# onion_dip_v21.net
KiCad netlist of a schematic drawn in EAGLE
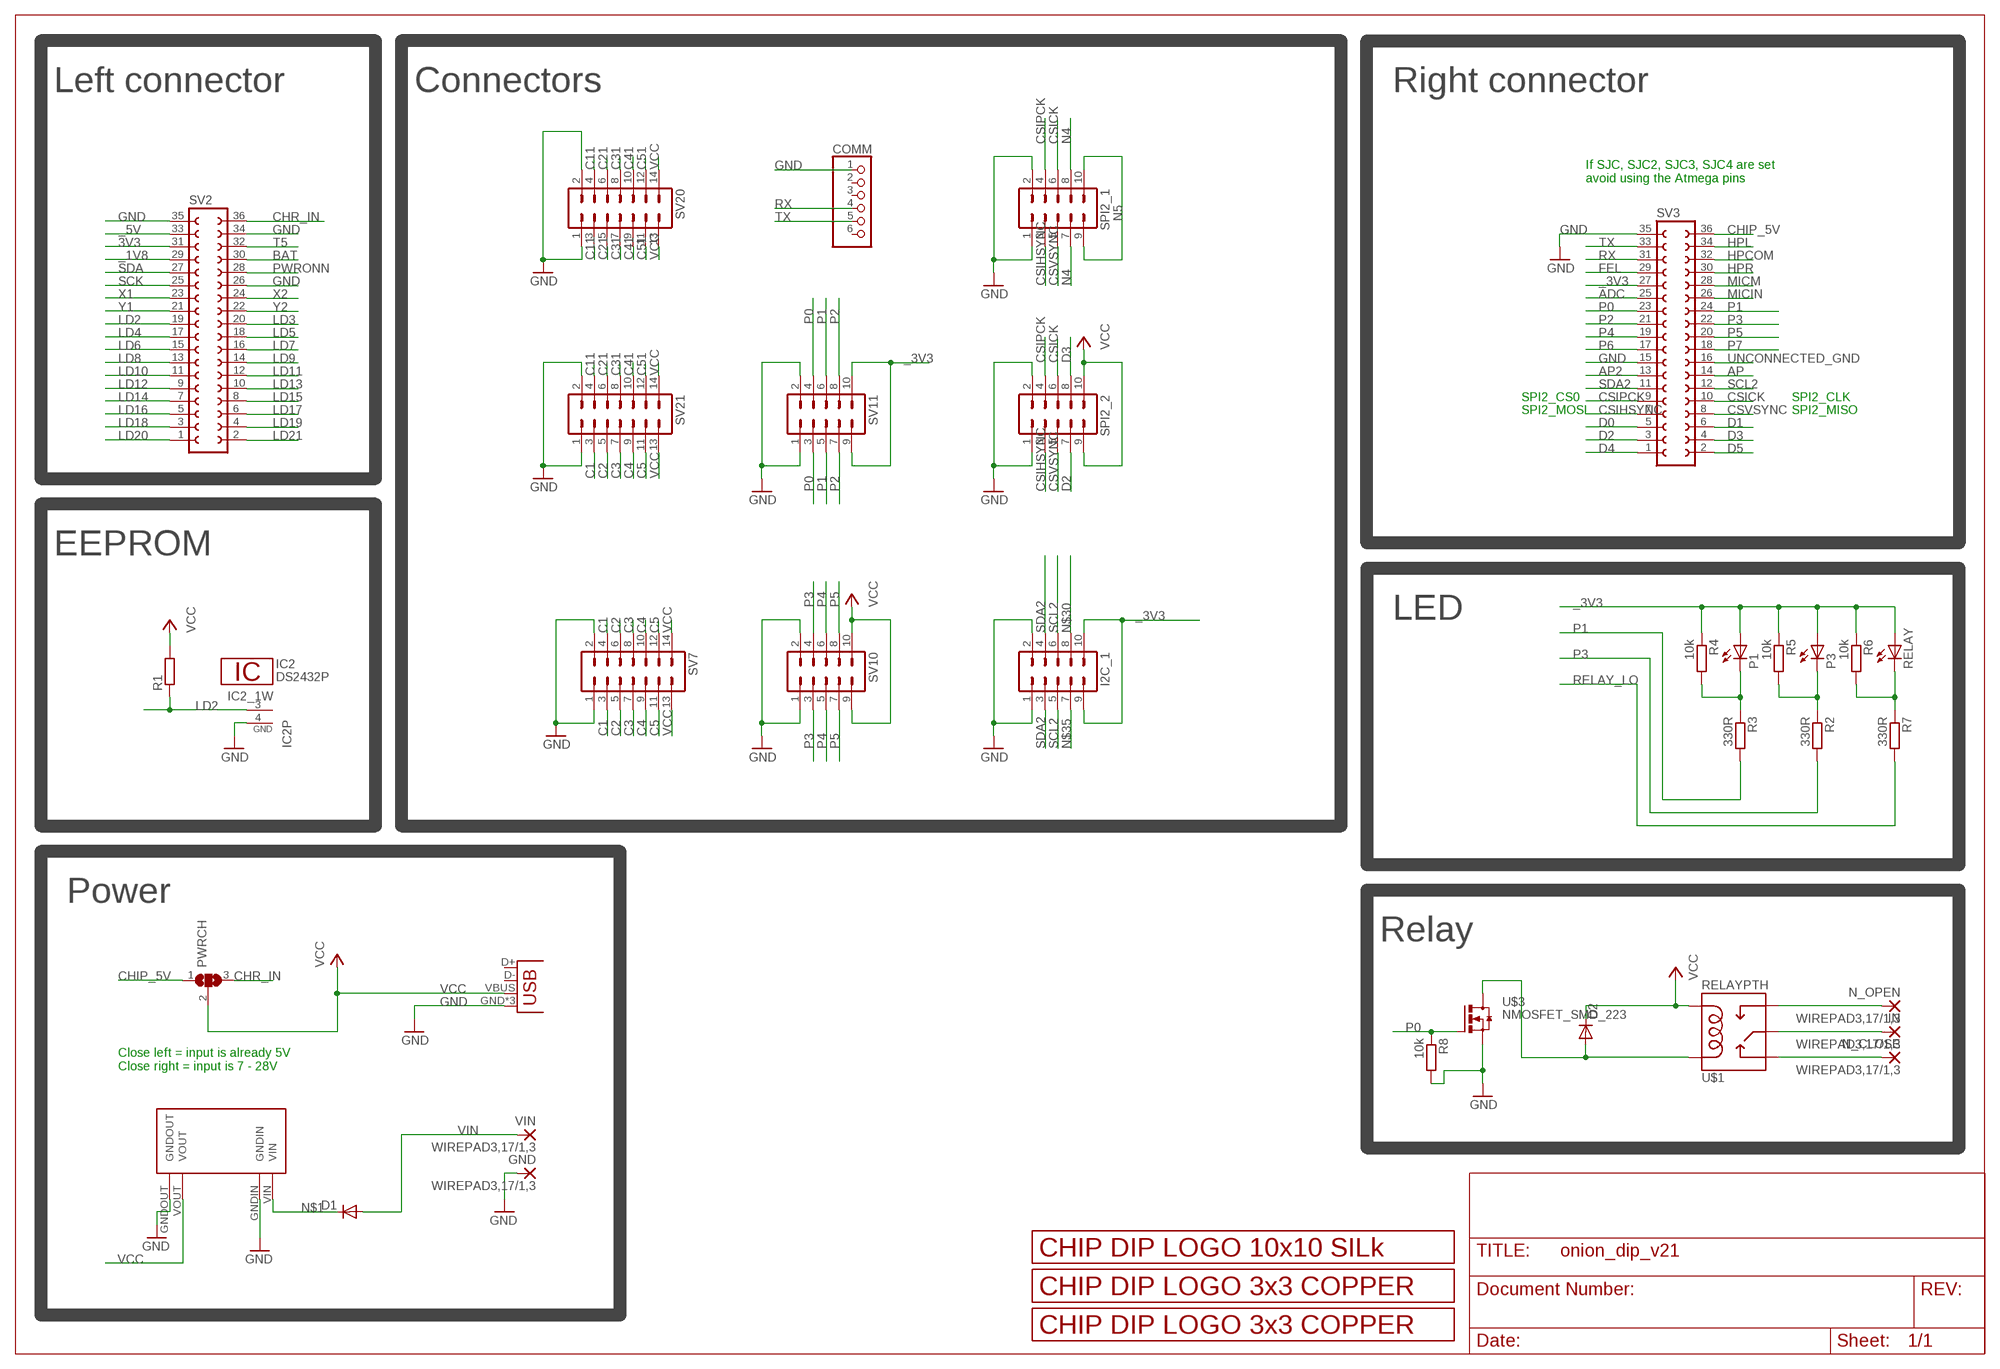
[diagram p0: schematic, sheet 1]

(export (version "E")
  (design (tool "Eeschema 10.0.6"))
  (components
    (comp (ref "COMM")
      (value "PINHD-1X6")
      (footprint "eagle-import:1X06")
      (libsource (lib "eagle-import") (part "PINHD-1X6"))
    )
    (comp (ref "D1")
      (value "DIODE-SMB")
      (footprint "eagle-import:SMB")
      (libsource (lib "eagle-import") (part "DIODE-SMB"))
    )
    (comp (ref "D2")
      (value "DIODE-SMB")
      (footprint "eagle-import:SMB")
      (libsource (lib "eagle-import") (part "DIODE-SMB"))
    )
    (comp (ref "GND")
      (value "WIREPAD3,17/1,3")
      (footprint "eagle-import:3,17_1,3")
      (libsource (lib "eagle-import") (part "WIREPAD3,17/1,3"))
    )
    (comp (ref "I2C_1")
      (value "MA05-2")
      (footprint "eagle-import:MA05-2")
      (libsource (lib "eagle-import") (part "MA05-2"))
    )
    (comp (ref "IC2")
      (value "DS2432P")
      (footprint "eagle-import:TSOC6")
      (libsource (lib "eagle-import") (part "DS2432P"))
    )
    (comp (ref "IN")
      (value "WIREPAD3,17/1,3")
      (footprint "eagle-import:3,17_1,3")
      (libsource (lib "eagle-import") (part "WIREPAD3,17/1,3"))
    )
    (comp (ref "N_CLOSE")
      (value "WIREPAD3,17/1,3")
      (footprint "eagle-import:3,17_1,3")
      (libsource (lib "eagle-import") (part "WIREPAD3,17/1,3"))
    )
    (comp (ref "N_OPEN")
      (value "WIREPAD3,17/1,3")
      (footprint "eagle-import:3,17_1,3")
      (libsource (lib "eagle-import") (part "WIREPAD3,17/1,3"))
    )
    (comp (ref "P1")
      (value "LEDCHIP-LED0805")
      (footprint "eagle-import:CHIP-LED0805")
      (libsource (lib "eagle-import") (part "LEDCHIP-LED0805"))
    )
    (comp (ref "P3")
      (value "LEDCHIP-LED0805")
      (footprint "eagle-import:CHIP-LED0805")
      (libsource (lib "eagle-import") (part "LEDCHIP-LED0805"))
    )
    (comp (ref "PWRCH")
      (value "SJ2W")
      (footprint "eagle-import:SJ_2")
      (libsource (lib "eagle-import") (part "SJ2W"))
    )
    (comp (ref "R1")
      (value "R-EU_R0805")
      (footprint "eagle-import:R0805")
      (libsource (lib "eagle-import") (part "R-EU_R0805"))
    )
    (comp (ref "R2")
      (value "330R")
      (footprint "eagle-import:R0805")
      (libsource (lib "eagle-import") (part "R-EU_R0805"))
    )
    (comp (ref "R3")
      (value "330R")
      (footprint "eagle-import:R0805")
      (libsource (lib "eagle-import") (part "R-EU_R0805"))
    )
    (comp (ref "R4")
      (value "10k")
      (footprint "eagle-import:R0805")
      (libsource (lib "eagle-import") (part "R-EU_R0805"))
    )
    (comp (ref "R5")
      (value "10k")
      (footprint "eagle-import:R0805")
      (libsource (lib "eagle-import") (part "R-EU_R0805"))
    )
    (comp (ref "R6")
      (value "10k")
      (footprint "eagle-import:R0805")
      (libsource (lib "eagle-import") (part "R-EU_R0805"))
    )
    (comp (ref "R7")
      (value "330R")
      (footprint "eagle-import:R0805")
      (libsource (lib "eagle-import") (part "R-EU_R0805"))
    )
    (comp (ref "R8")
      (value "10k")
      (footprint "eagle-import:R0805")
      (libsource (lib "eagle-import") (part "R-EU_R0805"))
    )
    (comp (ref "RELAY")
      (value "LEDCHIP-LED0805")
      (footprint "eagle-import:CHIP-LED0805")
      (libsource (lib "eagle-import") (part "LEDCHIP-LED0805"))
    )
    (comp (ref "SPI2_1")
      (value "MA05-2")
      (footprint "eagle-import:MA05-2")
      (libsource (lib "eagle-import") (part "MA05-2"))
    )
    (comp (ref "SPI2_2")
      (value "MA05-2")
      (footprint "eagle-import:MA05-2")
      (libsource (lib "eagle-import") (part "MA05-2"))
    )
    (comp (ref "SV2")
      (value "FE18-2")
      (footprint "eagle-import:FE18-2")
      (libsource (lib "eagle-import") (part "FE18-2"))
    )
    (comp (ref "SV3")
      (value "FE18-2")
      (footprint "eagle-import:FE18-2")
      (libsource (lib "eagle-import") (part "FE18-2"))
    )
    (comp (ref "SV7")
      (value "MA07-2")
      (footprint "eagle-import:MA07-2")
      (libsource (lib "eagle-import") (part "MA07-2"))
    )
    (comp (ref "SV10")
      (value "MA05-2")
      (footprint "eagle-import:MA05-2")
      (libsource (lib "eagle-import") (part "MA05-2"))
    )
    (comp (ref "SV11")
      (value "MA05-2")
      (footprint "eagle-import:MA05-2")
      (libsource (lib "eagle-import") (part "MA05-2"))
    )
    (comp (ref "SV20")
      (value "MA07-2")
      (footprint "eagle-import:MA07-2")
      (libsource (lib "eagle-import") (part "MA07-2"))
    )
    (comp (ref "SV21")
      (value "MA07-2")
      (footprint "eagle-import:MA07-2")
      (libsource (lib "eagle-import") (part "MA07-2"))
    )
    (comp (ref "U$1")
      (value "RELAYPTH")
      (footprint "eagle-import:SRD-05VDC-SL-C")
      (libsource (lib "eagle-import") (part "RELAYPTH"))
    )
    (comp (ref "U$3")
      (value "NMOSFET_SMD_223")
      (footprint "eagle-import:SOT223")
      (libsource (lib "eagle-import") (part "NMOSFET_SMD_223"))
    )
    (comp (ref "U$4")
      (value "LOGO_3X3_COPPER")
      (footprint "eagle-import:LOGO_3X3_COPPER")
      (libsource (lib "eagle-import") (part "LOGO_3X3_COPPER"))
    )
    (comp (ref "U$5")
      (value "LOGO_10X10_SILK")
      (footprint "eagle-import:LOGO_10X10_SILK")
      (libsource (lib "eagle-import") (part "LOGO_10X10_SILK"))
    )
    (comp (ref "U$6")
      (value "LOGO_3X3_COPPER")
      (footprint "eagle-import:LOGO_3X3_COPPER")
      (libsource (lib "eagle-import") (part "LOGO_3X3_COPPER"))
    )
    (comp (ref "U$9")
      (value "MP1584EN_FRAMELESS")
      (footprint "eagle-import:MP1584EN_FRAMELESS")
      (libsource (lib "eagle-import") (part "MP1584EN_FRAMELESS"))
    )
    (comp (ref "USB")
      (value "USBUSB-MICROB-SMT-DIP")
      (footprint "eagle-import:USB-MICROB-SMT-DIP")
      (libsource (lib "eagle-import") (part "USBUSB-MICROB-SMT-DIP"))
    )
    (comp (ref "VIN")
      (value "WIREPAD3,17/1,3")
      (footprint "eagle-import:3,17_1,3")
      (libsource (lib "eagle-import") (part "WIREPAD3,17/1,3"))
    )
  )
  (nets
    (net (code "1") (name "/3V3") (class "Default")
      (node (ref "SV2") (pin "31") (pinfunction "31_31") (pintype "passive"))
    )
    (net (code "2") (name "/ADC") (class "Default")
      (node (ref "SV3") (pin "25") (pinfunction "25_25") (pintype "passive"))
    )
    (net (code "3") (name "/AP") (class "Default")
      (node (ref "SV3") (pin "14") (pinfunction "14_14") (pintype "passive"))
    )
    (net (code "4") (name "/AP2") (class "Default")
      (node (ref "SV3") (pin "13") (pinfunction "13_13") (pintype "passive"))
    )
    (net (code "5") (name "/BAT") (class "Default")
      (node (ref "SV2") (pin "30") (pinfunction "30_30") (pintype "passive"))
    )
    (net (code "6") (name "/C1") (class "Default")
      (node (ref "SV21") (pin "3") (pinfunction "3_3") (pintype "passive"))
      (node (ref "SV7") (pin "3") (pinfunction "3_3") (pintype "passive"))
      (node (ref "SV7") (pin "4") (pinfunction "4_4") (pintype "passive"))
    )
    (net (code "7") (name "/C2") (class "Default")
      (node (ref "SV21") (pin "5") (pinfunction "5_5") (pintype "passive"))
      (node (ref "SV7") (pin "5") (pinfunction "5_5") (pintype "passive"))
      (node (ref "SV7") (pin "6") (pinfunction "6_6") (pintype "passive"))
    )
    (net (code "8") (name "/C3") (class "Default")
      (node (ref "SV21") (pin "7") (pinfunction "7_7") (pintype "passive"))
      (node (ref "SV7") (pin "7") (pinfunction "7_7") (pintype "passive"))
      (node (ref "SV7") (pin "8") (pinfunction "8_8") (pintype "passive"))
    )
    (net (code "9") (name "/C4") (class "Default")
      (node (ref "SV21") (pin "9") (pinfunction "9_9") (pintype "passive"))
      (node (ref "SV7") (pin "10") (pinfunction "10_10") (pintype "passive"))
      (node (ref "SV7") (pin "9") (pinfunction "9_9") (pintype "passive"))
    )
    (net (code "10") (name "/C5") (class "Default")
      (node (ref "SV21") (pin "11") (pinfunction "11_11") (pintype "passive"))
      (node (ref "SV7") (pin "11") (pinfunction "11_11") (pintype "passive"))
      (node (ref "SV7") (pin "12") (pinfunction "12_12") (pintype "passive"))
    )
    (net (code "11") (name "/C11") (class "Default")
      (node (ref "SV20") (pin "3") (pinfunction "3_3") (pintype "passive"))
      (node (ref "SV20") (pin "4") (pinfunction "4_4") (pintype "passive"))
      (node (ref "SV21") (pin "4") (pinfunction "4_4") (pintype "passive"))
    )
    (net (code "12") (name "/C21") (class "Default")
      (node (ref "SV20") (pin "5") (pinfunction "5_5") (pintype "passive"))
      (node (ref "SV20") (pin "6") (pinfunction "6_6") (pintype "passive"))
      (node (ref "SV21") (pin "6") (pinfunction "6_6") (pintype "passive"))
    )
    (net (code "13") (name "/C31") (class "Default")
      (node (ref "SV20") (pin "7") (pinfunction "7_7") (pintype "passive"))
      (node (ref "SV20") (pin "8") (pinfunction "8_8") (pintype "passive"))
      (node (ref "SV21") (pin "8") (pinfunction "8_8") (pintype "passive"))
    )
    (net (code "14") (name "/C41") (class "Default")
      (node (ref "SV20") (pin "10") (pinfunction "10_10") (pintype "passive"))
      (node (ref "SV20") (pin "9") (pinfunction "9_9") (pintype "passive"))
      (node (ref "SV21") (pin "10") (pinfunction "10_10") (pintype "passive"))
    )
    (net (code "15") (name "/C51") (class "Default")
      (node (ref "SV20") (pin "11") (pinfunction "11_11") (pintype "passive"))
      (node (ref "SV20") (pin "12") (pinfunction "12_12") (pintype "passive"))
      (node (ref "SV21") (pin "12") (pinfunction "12_12") (pintype "passive"))
    )
    (net (code "16") (name "/CHIP_5V") (class "Default")
      (node (ref "PWRCH") (pin "1") (pinfunction "1_1") (pintype "passive"))
      (node (ref "SV3") (pin "36") (pinfunction "36_36") (pintype "passive"))
    )
    (net (code "17") (name "/CHR_IN") (class "Default")
      (node (ref "PWRCH") (pin "3") (pinfunction "3_3") (pintype "passive"))
      (node (ref "SV2") (pin "36") (pinfunction "36_36") (pintype "passive"))
    )
    (net (code "18") (name "/CSICK") (class "Default")
      (node (ref "SPI2_1") (pin "6") (pinfunction "6_6") (pintype "passive"))
      (node (ref "SPI2_2") (pin "6") (pinfunction "6_6") (pintype "passive"))
      (node (ref "SV3") (pin "10") (pinfunction "10_10") (pintype "passive"))
    )
    (net (code "19") (name "/CSIHSYNC") (class "Default")
      (node (ref "SPI2_1") (pin "3") (pinfunction "3_3") (pintype "passive"))
      (node (ref "SPI2_2") (pin "3") (pinfunction "3_3") (pintype "passive"))
      (node (ref "SV3") (pin "7") (pinfunction "7_7") (pintype "passive"))
    )
    (net (code "20") (name "/CSIPCK") (class "Default")
      (node (ref "SPI2_1") (pin "4") (pinfunction "4_4") (pintype "passive"))
      (node (ref "SPI2_2") (pin "4") (pinfunction "4_4") (pintype "passive"))
      (node (ref "SV3") (pin "9") (pinfunction "9_9") (pintype "passive"))
    )
    (net (code "21") (name "/CSVSYNC") (class "Default")
      (node (ref "SPI2_1") (pin "5") (pinfunction "5_5") (pintype "passive"))
      (node (ref "SPI2_2") (pin "5") (pinfunction "5_5") (pintype "passive"))
      (node (ref "SV3") (pin "8") (pinfunction "8_8") (pintype "passive"))
    )
    (net (code "22") (name "/D0") (class "Default")
      (node (ref "SV3") (pin "5") (pinfunction "5_5") (pintype "passive"))
    )
    (net (code "23") (name "/D1") (class "Default")
      (node (ref "SV3") (pin "6") (pinfunction "6_6") (pintype "passive"))
    )
    (net (code "24") (name "/D2") (class "Default")
      (node (ref "SPI2_2") (pin "7") (pinfunction "7_7") (pintype "passive"))
      (node (ref "SV3") (pin "3") (pinfunction "3_3") (pintype "passive"))
    )
    (net (code "25") (name "/D3") (class "Default")
      (node (ref "SPI2_2") (pin "8") (pinfunction "8_8") (pintype "passive"))
      (node (ref "SV3") (pin "4") (pinfunction "4_4") (pintype "passive"))
    )
    (net (code "26") (name "/D4") (class "Default")
      (node (ref "SV3") (pin "1") (pinfunction "1_1") (pintype "passive"))
    )
    (net (code "27") (name "/D5") (class "Default")
      (node (ref "SV3") (pin "2") (pinfunction "2_2") (pintype "passive"))
    )
    (net (code "28") (name "/FEL") (class "Default")
      (node (ref "SV3") (pin "29") (pinfunction "29_29") (pintype "passive"))
    )
    (net (code "29") (name "/HPCOM") (class "Default")
      (node (ref "SV3") (pin "32") (pinfunction "32_32") (pintype "passive"))
    )
    (net (code "30") (name "/HPL") (class "Default")
      (node (ref "SV3") (pin "34") (pinfunction "34_34") (pintype "passive"))
    )
    (net (code "31") (name "/HPR") (class "Default")
      (node (ref "SV3") (pin "30") (pinfunction "30_30") (pintype "passive"))
    )
    (net (code "32") (name "/LD2") (class "Default")
      (node (ref "IC2") (pin "3") (pinfunction "1W_3") (pintype "power_in"))
      (node (ref "R1") (pin "1") (pinfunction "1_1") (pintype "passive"))
      (node (ref "SV2") (pin "19") (pinfunction "19_19") (pintype "passive"))
    )
    (net (code "33") (name "/LD3") (class "Default")
      (node (ref "SV2") (pin "20") (pinfunction "20_20") (pintype "passive"))
    )
    (net (code "34") (name "/LD4") (class "Default")
      (node (ref "SV2") (pin "17") (pinfunction "17_17") (pintype "passive"))
    )
    (net (code "35") (name "/LD5") (class "Default")
      (node (ref "SV2") (pin "18") (pinfunction "18_18") (pintype "passive"))
    )
    (net (code "36") (name "/LD6") (class "Default")
      (node (ref "SV2") (pin "15") (pinfunction "15_15") (pintype "passive"))
    )
    (net (code "37") (name "/LD7") (class "Default")
      (node (ref "SV2") (pin "16") (pinfunction "16_16") (pintype "passive"))
    )
    (net (code "38") (name "/LD8") (class "Default")
      (node (ref "SV2") (pin "13") (pinfunction "13_13") (pintype "passive"))
    )
    (net (code "39") (name "/LD9") (class "Default")
      (node (ref "SV2") (pin "14") (pinfunction "14_14") (pintype "passive"))
    )
    (net (code "40") (name "/LD10") (class "Default")
      (node (ref "SV2") (pin "11") (pinfunction "11_11") (pintype "passive"))
    )
    (net (code "41") (name "/LD11") (class "Default")
      (node (ref "SV2") (pin "12") (pinfunction "12_12") (pintype "passive"))
    )
    (net (code "42") (name "/LD12") (class "Default")
      (node (ref "SV2") (pin "9") (pinfunction "9_9") (pintype "passive"))
    )
    (net (code "43") (name "/LD13") (class "Default")
      (node (ref "SV2") (pin "10") (pinfunction "10_10") (pintype "passive"))
    )
    (net (code "44") (name "/LD14") (class "Default")
      (node (ref "SV2") (pin "7") (pinfunction "7_7") (pintype "passive"))
    )
    (net (code "45") (name "/LD15") (class "Default")
      (node (ref "SV2") (pin "8") (pinfunction "8_8") (pintype "passive"))
    )
    (net (code "46") (name "/LD16") (class "Default")
      (node (ref "SV2") (pin "5") (pinfunction "5_5") (pintype "passive"))
    )
    (net (code "47") (name "/LD17") (class "Default")
      (node (ref "SV2") (pin "6") (pinfunction "6_6") (pintype "passive"))
    )
    (net (code "48") (name "/LD18") (class "Default")
      (node (ref "SV2") (pin "3") (pinfunction "3_3") (pintype "passive"))
    )
    (net (code "49") (name "/LD19") (class "Default")
      (node (ref "SV2") (pin "4") (pinfunction "4_4") (pintype "passive"))
    )
    (net (code "50") (name "/LD20") (class "Default")
      (node (ref "SV2") (pin "1") (pinfunction "1_1") (pintype "passive"))
    )
    (net (code "51") (name "/LD21") (class "Default")
      (node (ref "SV2") (pin "2") (pinfunction "2_2") (pintype "passive"))
    )
    (net (code "52") (name "/MICIN") (class "Default")
      (node (ref "SV3") (pin "26") (pinfunction "26_26") (pintype "passive"))
    )
    (net (code "53") (name "/MICM") (class "Default")
      (node (ref "SV3") (pin "28") (pinfunction "28_28") (pintype "passive"))
    )
    (net (code "54") (name "/N$1") (class "Default")
      (node (ref "D1") (pin "C") (pinfunction "C_C") (pintype "passive"))
      (node (ref "U$9") (pin "VIN") (pinfunction "VIN_VIN") (pintype "power_in"))
    )
    (net (code "55") (name "/N$30") (class "Default")
      (node (ref "I2C_1") (pin "8") (pinfunction "8_8") (pintype "passive"))
    )
    (net (code "56") (name "/N$35") (class "Default")
      (node (ref "I2C_1") (pin "7") (pinfunction "7_7") (pintype "passive"))
    )
    (net (code "57") (name "/N4") (class "Default")
      (node (ref "SPI2_1") (pin "7") (pinfunction "7_7") (pintype "passive"))
      (node (ref "SPI2_1") (pin "8") (pinfunction "8_8") (pintype "passive"))
    )
    (net (code "58") (name "/N5") (class "Default")
      (node (ref "SPI2_1") (pin "10") (pinfunction "10_10") (pintype "passive"))
      (node (ref "SPI2_1") (pin "9") (pinfunction "9_9") (pintype "passive"))
    )
    (net (code "59") (name "/P0") (class "Default")
      (node (ref "R8") (pin "1") (pinfunction "1_1") (pintype "passive"))
      (node (ref "SV11") (pin "3") (pinfunction "3_3") (pintype "passive"))
      (node (ref "SV11") (pin "4") (pinfunction "4_4") (pintype "passive"))
      (node (ref "SV3") (pin "23") (pinfunction "23_23") (pintype "passive"))
      (node (ref "U$3") (pin "1") (pinfunction "G_1") (pintype "passive"))
    )
    (net (code "60") (name "/P1") (class "Default")
      (node (ref "R3") (pin "2") (pinfunction "2_2") (pintype "passive"))
      (node (ref "SV11") (pin "5") (pinfunction "5_5") (pintype "passive"))
      (node (ref "SV11") (pin "6") (pinfunction "6_6") (pintype "passive"))
      (node (ref "SV3") (pin "24") (pinfunction "24_24") (pintype "passive"))
    )
    (net (code "61") (name "/P2") (class "Default")
      (node (ref "SV11") (pin "7") (pinfunction "7_7") (pintype "passive"))
      (node (ref "SV11") (pin "8") (pinfunction "8_8") (pintype "passive"))
      (node (ref "SV3") (pin "21") (pinfunction "21_21") (pintype "passive"))
    )
    (net (code "62") (name "/P3") (class "Default")
      (node (ref "R2") (pin "2") (pinfunction "2_2") (pintype "passive"))
      (node (ref "SV10") (pin "3") (pinfunction "3_3") (pintype "passive"))
      (node (ref "SV10") (pin "4") (pinfunction "4_4") (pintype "passive"))
      (node (ref "SV3") (pin "22") (pinfunction "22_22") (pintype "passive"))
    )
    (net (code "63") (name "/P4") (class "Default")
      (node (ref "SV10") (pin "5") (pinfunction "5_5") (pintype "passive"))
      (node (ref "SV10") (pin "6") (pinfunction "6_6") (pintype "passive"))
      (node (ref "SV3") (pin "19") (pinfunction "19_19") (pintype "passive"))
    )
    (net (code "64") (name "/P5") (class "Default")
      (node (ref "SV10") (pin "7") (pinfunction "7_7") (pintype "passive"))
      (node (ref "SV10") (pin "8") (pinfunction "8_8") (pintype "passive"))
      (node (ref "SV3") (pin "20") (pinfunction "20_20") (pintype "passive"))
    )
    (net (code "65") (name "/P6") (class "Default")
      (node (ref "SV3") (pin "17") (pinfunction "17_17") (pintype "passive"))
    )
    (net (code "66") (name "/P7") (class "Default")
      (node (ref "SV3") (pin "18") (pinfunction "18_18") (pintype "passive"))
    )
    (net (code "67") (name "/PWRONN") (class "Default")
      (node (ref "SV2") (pin "28") (pinfunction "28_28") (pintype "passive"))
    )
    (net (code "68") (name "/RELAY_LO") (class "Default")
      (node (ref "D2") (pin "A") (pinfunction "A_A") (pintype "passive"))
      (node (ref "R7") (pin "2") (pinfunction "2_2") (pintype "passive"))
      (node (ref "U$1") (pin "COIL1") (pinfunction "COIL1_COIL1") (pintype "bidirectional"))
      (node (ref "U$3") (pin "2") (pinfunction "D_2") (pintype "passive"))
      (node (ref "U$3") (pin "4") (pinfunction "D_4") (pintype "passive"))
    )
    (net (code "69") (name "/RX") (class "Default")
      (node (ref "COMM") (pin "4") (pinfunction "4_4") (pintype "passive"))
      (node (ref "SV3") (pin "31") (pinfunction "31_31") (pintype "passive"))
    )
    (net (code "70") (name "/SCK") (class "Default")
      (node (ref "SV2") (pin "25") (pinfunction "25_25") (pintype "passive"))
    )
    (net (code "71") (name "/SCL2") (class "Default")
      (node (ref "I2C_1") (pin "5") (pinfunction "5_5") (pintype "passive"))
      (node (ref "I2C_1") (pin "6") (pinfunction "6_6") (pintype "passive"))
      (node (ref "SV3") (pin "12") (pinfunction "12_12") (pintype "passive"))
    )
    (net (code "72") (name "/SDA") (class "Default")
      (node (ref "SV2") (pin "27") (pinfunction "27_27") (pintype "passive"))
    )
    (net (code "73") (name "/SDA2") (class "Default")
      (node (ref "I2C_1") (pin "3") (pinfunction "3_3") (pintype "passive"))
      (node (ref "I2C_1") (pin "4") (pinfunction "4_4") (pintype "passive"))
      (node (ref "SV3") (pin "11") (pinfunction "11_11") (pintype "passive"))
    )
    (net (code "74") (name "/T5") (class "Default")
      (node (ref "SV2") (pin "32") (pinfunction "32_32") (pintype "passive"))
    )
    (net (code "75") (name "/TX") (class "Default")
      (node (ref "COMM") (pin "5") (pinfunction "5_5") (pintype "passive"))
      (node (ref "SV3") (pin "33") (pinfunction "33_33") (pintype "passive"))
    )
    (net (code "76") (name "/UNCONNECTED_GND") (class "Default")
      (node (ref "SV3") (pin "16") (pinfunction "16_16") (pintype "passive"))
    )
    (net (code "77") (name "/VIN") (class "Default")
      (node (ref "D1") (pin "A") (pinfunction "A_A") (pintype "passive"))
      (node (ref "VIN") (pin "1") (pinfunction "P_1") (pintype "passive"))
    )
    (net (code "78") (name "/X1") (class "Default")
      (node (ref "SV2") (pin "23") (pinfunction "23_23") (pintype "passive"))
    )
    (net (code "79") (name "/X2") (class "Default")
      (node (ref "SV2") (pin "24") (pinfunction "24_24") (pintype "passive"))
    )
    (net (code "80") (name "/Y1") (class "Default")
      (node (ref "SV2") (pin "21") (pinfunction "21_21") (pintype "passive"))
    )
    (net (code "81") (name "/Y2") (class "Default")
      (node (ref "SV2") (pin "22") (pinfunction "22_22") (pintype "passive"))
    )
    (net (code "82") (name "/_1V8") (class "Default")
      (node (ref "SV2") (pin "29") (pinfunction "29_29") (pintype "passive"))
    )
    (net (code "83") (name "/_3V3") (class "Default")
      (node (ref "I2C_1") (pin "10") (pinfunction "10_10") (pintype "passive"))
      (node (ref "I2C_1") (pin "9") (pinfunction "9_9") (pintype "passive"))
      (node (ref "P1") (pin "A") (pinfunction "A_A") (pintype "passive"))
      (node (ref "P3") (pin "A") (pinfunction "A_A") (pintype "passive"))
      (node (ref "R4") (pin "1") (pinfunction "1_1") (pintype "passive"))
      (node (ref "R5") (pin "1") (pinfunction "1_1") (pintype "passive"))
      (node (ref "R6") (pin "1") (pinfunction "1_1") (pintype "passive"))
      (node (ref "RELAY") (pin "A") (pinfunction "A_A") (pintype "passive"))
      (node (ref "SV11") (pin "10") (pinfunction "10_10") (pintype "passive"))
      (node (ref "SV11") (pin "9") (pinfunction "9_9") (pintype "passive"))
      (node (ref "SV3") (pin "27") (pinfunction "27_27") (pintype "passive"))
    )
    (net (code "84") (name "/_5V") (class "Default")
      (node (ref "SV2") (pin "33") (pinfunction "33_33") (pintype "passive"))
    )
    (net (code "85") (name "GND") (class "Default")
      (node (ref "COMM") (pin "1") (pinfunction "1_1") (pintype "passive"))
      (node (ref "GND") (pin "1") (pinfunction "P_1") (pintype "passive"))
      (node (ref "I2C_1") (pin "1") (pinfunction "1_1") (pintype "passive"))
      (node (ref "I2C_1") (pin "2") (pinfunction "2_2") (pintype "passive"))
      (node (ref "IC2") (pin "4") (pinfunction "GND_4") (pintype "power_in"))
      (node (ref "R8") (pin "2") (pinfunction "2_2") (pintype "passive"))
      (node (ref "SPI2_1") (pin "1") (pinfunction "1_1") (pintype "passive"))
      (node (ref "SPI2_1") (pin "2") (pinfunction "2_2") (pintype "passive"))
      (node (ref "SPI2_2") (pin "1") (pinfunction "1_1") (pintype "passive"))
      (node (ref "SPI2_2") (pin "2") (pinfunction "2_2") (pintype "passive"))
      (node (ref "SV10") (pin "1") (pinfunction "1_1") (pintype "passive"))
      (node (ref "SV10") (pin "2") (pinfunction "2_2") (pintype "passive"))
      (node (ref "SV11") (pin "1") (pinfunction "1_1") (pintype "passive"))
      (node (ref "SV11") (pin "2") (pinfunction "2_2") (pintype "passive"))
      (node (ref "SV2") (pin "26") (pinfunction "26_26") (pintype "passive"))
      (node (ref "SV2") (pin "34") (pinfunction "34_34") (pintype "passive"))
      (node (ref "SV2") (pin "35") (pinfunction "35_35") (pintype "passive"))
      (node (ref "SV20") (pin "1") (pinfunction "1_1") (pintype "passive"))
      (node (ref "SV20") (pin "2") (pinfunction "2_2") (pintype "passive"))
      (node (ref "SV21") (pin "1") (pinfunction "1_1") (pintype "passive"))
      (node (ref "SV21") (pin "2") (pinfunction "2_2") (pintype "passive"))
      (node (ref "SV3") (pin "15") (pinfunction "15_15") (pintype "passive"))
      (node (ref "SV3") (pin "35") (pinfunction "35_35") (pintype "passive"))
      (node (ref "SV7") (pin "1") (pinfunction "1_1") (pintype "passive"))
      (node (ref "SV7") (pin "2") (pinfunction "2_2") (pintype "passive"))
      (node (ref "U$3") (pin "3") (pinfunction "S_3") (pintype "passive"))
      (node (ref "U$9") (pin "GNDIN") (pinfunction "GNDIN_GNDIN") (pintype "power_in"))
      (node (ref "U$9") (pin "GNDOUT") (pinfunction "GNDOUT_GNDOUT") (pintype "power_in"))
      (node (ref "USB") (pin "GND") (pinfunction "GND_GND") (pintype "bidirectional"))
      (node (ref "USB") (pin "MT1") (pinfunction "GND_MT1") (pintype "bidirectional"))
      (node (ref "USB") (pin "MT2") (pinfunction "GND_MT2") (pintype "bidirectional"))
    )
    (net (code "86") (name "Net-(IN-P)") (class "Default")
      (node (ref "IN") (pin "1") (pinfunction "P_1") (pintype "passive"))
      (node (ref "U$1") (pin "SWCOMMON") (pinfunction "SWCOMMON_SWCOMMON") (pintype "bidirectional"))
    )
    (net (code "87") (name "Net-(N_CLOSE-P)") (class "Default")
      (node (ref "N_CLOSE") (pin "1") (pinfunction "P_1") (pintype "passive"))
      (node (ref "U$1") (pin "SWCLOSED") (pinfunction "SWCLOSE_SWCLOSED") (pintype "bidirectional"))
    )
    (net (code "88") (name "Net-(N_OPEN-P)") (class "Default")
      (node (ref "N_OPEN") (pin "1") (pinfunction "P_1") (pintype "passive"))
      (node (ref "U$1") (pin "SWOPEN") (pinfunction "SWOPEN_SWOPEN") (pintype "bidirectional"))
    )
    (net (code "89") (name "Net-(P1-PadC)") (class "Default")
      (node (ref "P1") (pin "C") (pinfunction "C_C") (pintype "passive"))
      (node (ref "R3") (pin "1") (pinfunction "1_1") (pintype "passive"))
      (node (ref "R4") (pin "2") (pinfunction "2_2") (pintype "passive"))
    )
    (net (code "90") (name "Net-(P3-PadC)") (class "Default")
      (node (ref "P3") (pin "C") (pinfunction "C_C") (pintype "passive"))
      (node (ref "R2") (pin "1") (pinfunction "1_1") (pintype "passive"))
      (node (ref "R5") (pin "2") (pinfunction "2_2") (pintype "passive"))
    )
    (net (code "91") (name "Net-(R6-Pad2)") (class "Default")
      (node (ref "R6") (pin "2") (pinfunction "2_2") (pintype "passive"))
      (node (ref "R7") (pin "1") (pinfunction "1_1") (pintype "passive"))
      (node (ref "RELAY") (pin "C") (pinfunction "C_C") (pintype "passive"))
    )
    (net (code "92") (name "VCC") (class "Default")
      (node (ref "D2") (pin "C") (pinfunction "C_C") (pintype "passive"))
      (node (ref "PWRCH") (pin "2") (pinfunction "2_2") (pintype "passive"))
      (node (ref "R1") (pin "2") (pinfunction "2_2") (pintype "passive"))
      (node (ref "SPI2_2") (pin "10") (pinfunction "10_10") (pintype "passive"))
      (node (ref "SPI2_2") (pin "9") (pinfunction "9_9") (pintype "passive"))
      (node (ref "SV10") (pin "10") (pinfunction "10_10") (pintype "passive"))
      (node (ref "SV10") (pin "9") (pinfunction "9_9") (pintype "passive"))
      (node (ref "SV20") (pin "13") (pinfunction "13_13") (pintype "passive"))
      (node (ref "SV20") (pin "14") (pinfunction "14_14") (pintype "passive"))
      (node (ref "SV21") (pin "13") (pinfunction "13_13") (pintype "passive"))
      (node (ref "SV21") (pin "14") (pinfunction "14_14") (pintype "passive"))
      (node (ref "SV7") (pin "13") (pinfunction "13_13") (pintype "passive"))
      (node (ref "SV7") (pin "14") (pinfunction "14_14") (pintype "passive"))
      (node (ref "U$1") (pin "COIL0") (pinfunction "COIL0_COIL0") (pintype "bidirectional"))
      (node (ref "U$9") (pin "VOUT") (pinfunction "VOUT_VOUT") (pintype "power_in"))
      (node (ref "USB") (pin "VBUS") (pinfunction "VBUS_VBUS") (pintype "bidirectional"))
    )
    (net (code "93") (name "unconnected-(COMM-Pad2)") (class "Default")
      (node (ref "COMM") (pin "2") (pinfunction "2_2") (pintype "passive"))
    )
    (net (code "94") (name "unconnected-(COMM-Pad3)") (class "Default")
      (node (ref "COMM") (pin "3") (pinfunction "3_3") (pintype "passive"))
    )
    (net (code "95") (name "unconnected-(COMM-Pad6)") (class "Default")
      (node (ref "COMM") (pin "6") (pinfunction "6_6") (pintype "passive"))
    )
    (net (code "96") (name "unconnected-(USB-PadD+)") (class "Default")
      (node (ref "USB") (pin "D+") (pinfunction "D+_D+") (pintype "bidirectional"))
    )
    (net (code "97") (name "unconnected-(USB-PadD-)") (class "Default")
      (node (ref "USB") (pin "D-") (pinfunction "D-_D-") (pintype "bidirectional"))
    )
  )
)
